# poe.net
KiCad netlist of a schematic drawn in EAGLE
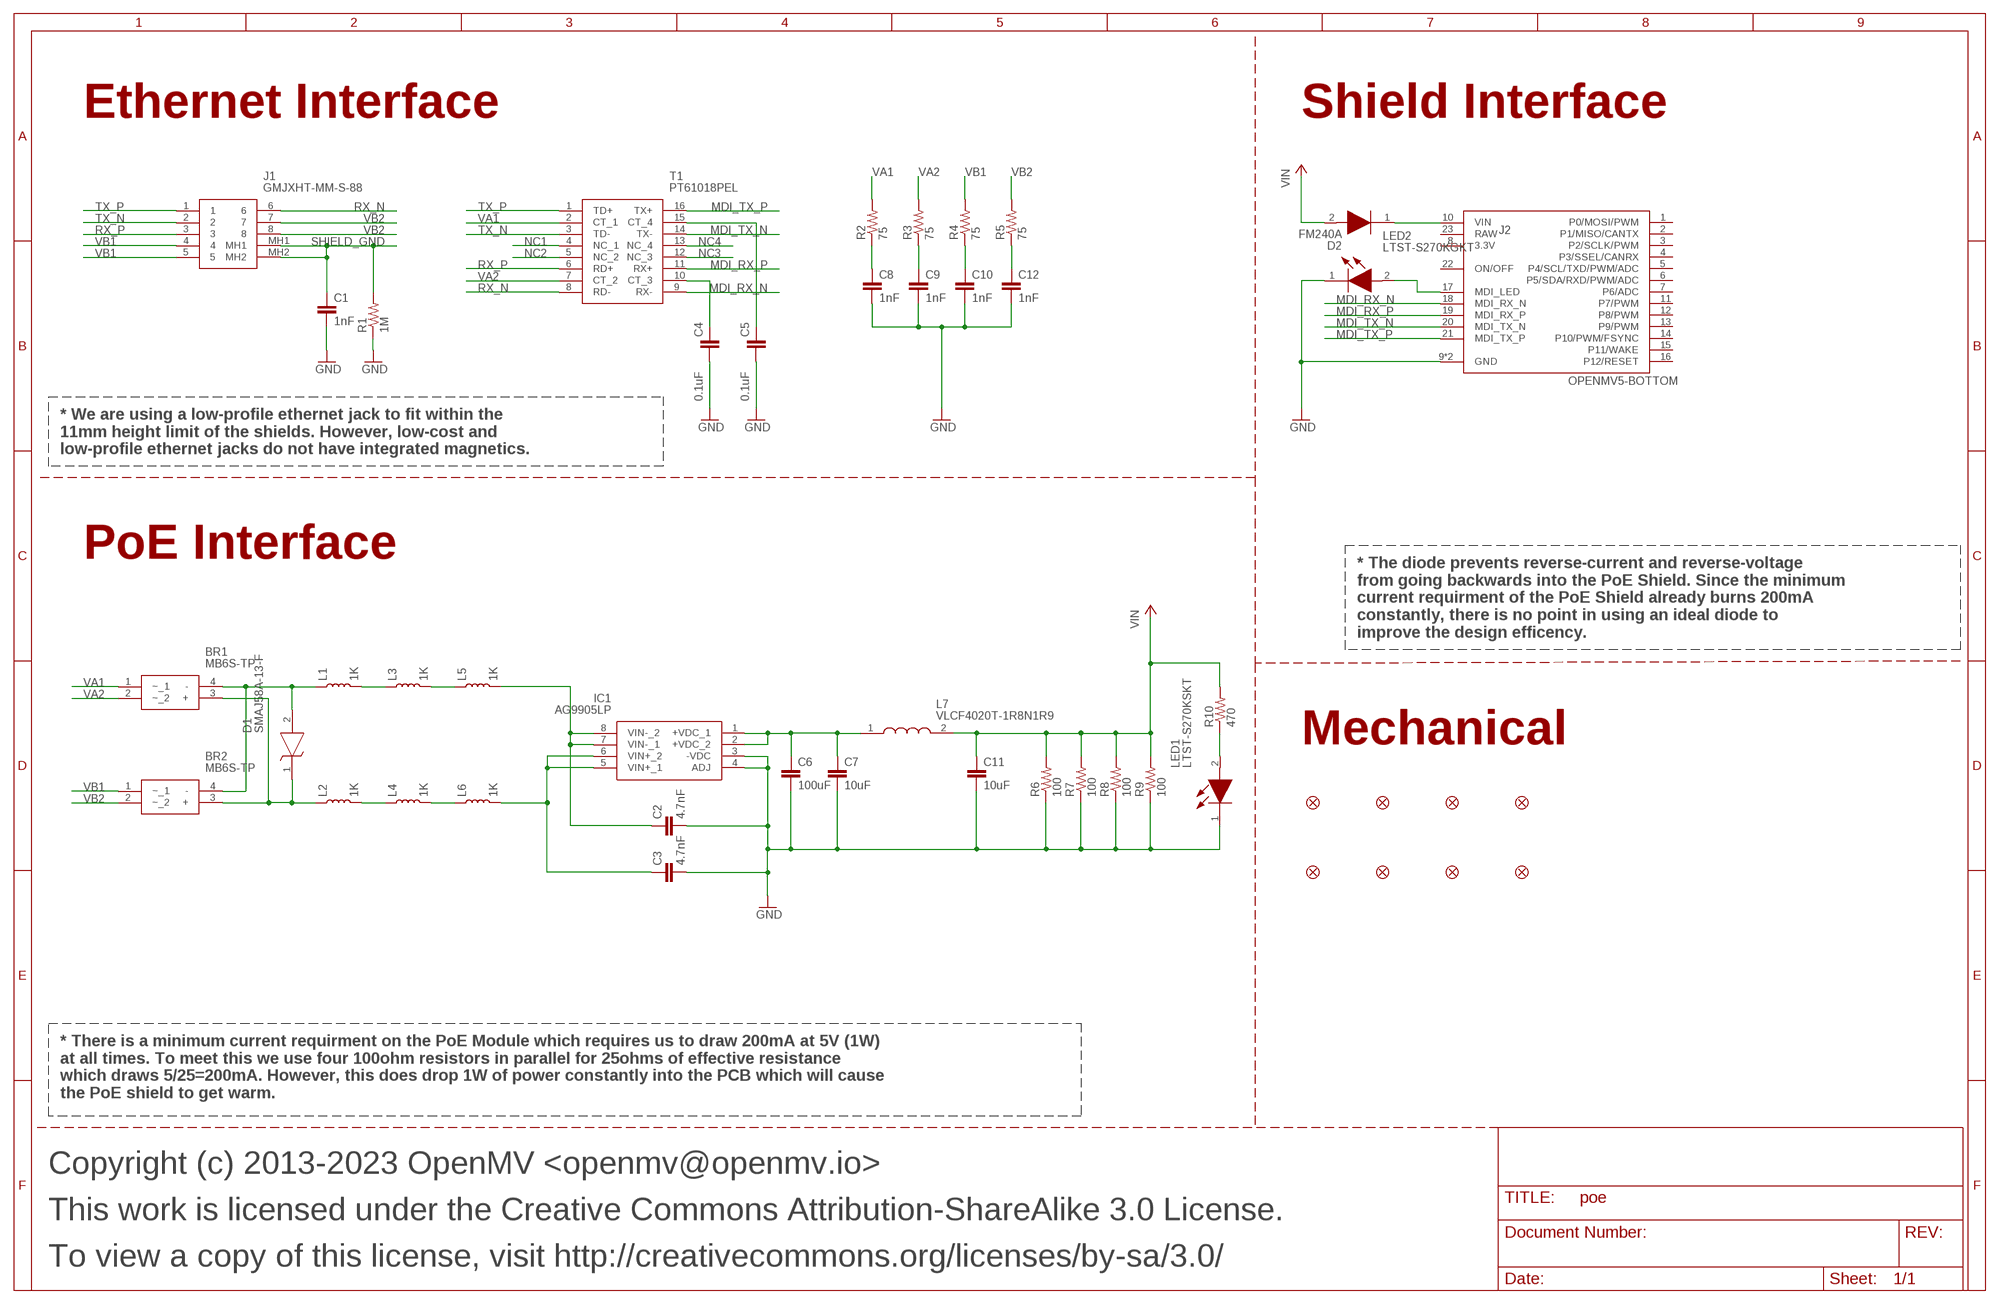
[diagram p0: schematic, sheet 1]

(export (version "E")
  (design (tool "Eeschema 10.0.6"))
  (components
    (comp (ref "BR1")
      (value "MB6S-TP")
      (footprint "eagle-import:SOP254P665X270-4N")
      (fields (field (name "MOUSER_PART_NUMBER") "833-MB6S-TP"))
      (libsource (lib "eagle-import") (part "MB6S-TP"))
    )
    (comp (ref "BR2")
      (value "MB6S-TP")
      (footprint "eagle-import:SOP254P665X270-4N")
      (fields (field (name "MOUSER_PART_NUMBER") "833-MB6S-TP"))
      (libsource (lib "eagle-import") (part "MB6S-TP"))
    )
    (comp (ref "C1")
      (value "1nF")
      (footprint "eagle-import:C1206")
      (fields (field (name "MPN") "1206B102K252CT"))
      (libsource (lib "eagle-import") (part "C-EUC1206"))
    )
    (comp (ref "C2")
      (value "4.7nF")
      (footprint "eagle-import:C1812")
      (fields (field (name "MPN") "202S43W472KV4E"))
      (libsource (lib "eagle-import") (part "C-EUC1812"))
    )
    (comp (ref "C3")
      (value "4.7nF")
      (footprint "eagle-import:C1812")
      (fields (field (name "MPN") "202S43W472KV4E"))
      (libsource (lib "eagle-import") (part "C-EUC1812"))
    )
    (comp (ref "C4")
      (value "0.1uF")
      (footprint "eagle-import:0402")
      (fields (field (name "MPN") "GRM155R71H104KE14D"))
      (libsource (lib "eagle-import") (part "0.1UF-0402-16V-10%"))
    )
    (comp (ref "C5")
      (value "0.1uF")
      (footprint "eagle-import:0402")
      (fields (field (name "MPN") "GRM155R71H104KE14D"))
      (libsource (lib "eagle-import") (part "0.1UF-0402-16V-10%"))
    )
    (comp (ref "C6")
      (value "100uF")
      (footprint "eagle-import:C1206")
      (fields (field (name "MPN") "CL31A107MQHNNWE"))
      (libsource (lib "eagle-import") (part "C-EUC1206"))
    )
    (comp (ref "C7")
      (value "10uF")
      (footprint "eagle-import:C0402")
      (fields (field (name "MPN") "GRM155R60J106ME05D"))
      (libsource (lib "eagle-import") (part "C-EUC0402"))
    )
    (comp (ref "C8")
      (value "1nF")
      (footprint "eagle-import:C1206")
      (fields (field (name "MPN") "1206B102K252CT"))
      (libsource (lib "eagle-import") (part "C-EUC1206"))
    )
    (comp (ref "C9")
      (value "1nF")
      (footprint "eagle-import:C1206")
      (fields (field (name "MPN") "1206B102K252CT"))
      (libsource (lib "eagle-import") (part "C-EUC1206"))
    )
    (comp (ref "C10")
      (value "1nF")
      (footprint "eagle-import:C1206")
      (fields (field (name "MPN") "1206B102K252CT"))
      (libsource (lib "eagle-import") (part "C-EUC1206"))
    )
    (comp (ref "C11")
      (value "10uF")
      (footprint "eagle-import:C0402")
      (fields (field (name "MPN") "GRM155R60J106ME05D"))
      (libsource (lib "eagle-import") (part "C-EUC0402"))
    )
    (comp (ref "C12")
      (value "1nF")
      (footprint "eagle-import:C1206")
      (fields (field (name "MPN") "1206B102K252CT"))
      (libsource (lib "eagle-import") (part "C-EUC1206"))
    )
    (comp (ref "D1")
      (value "SMAJ58A-13-F")
      (footprint "eagle-import:DIOM5226X230N")
      (fields (field (name "MOUSER_PART_NUMBER") "621-SMAJ58A-13-F") (field (name "MPN") "SMAJ58A/TR13"))
      (libsource (lib "eagle-import") (part "SMAJ58A-13-F"))
    )
    (comp (ref "D2")
      (value "FM240A")
      (footprint "eagle-import:DIOM5025X231N")
      (fields (field (name "MOUSER_PART_NUMBER") "583-FM240A"))
      (libsource (lib "eagle-import") (part "FM240A"))
    )
    (comp (ref "FD1")
      (value "FIDUCIAL1X2")
      (footprint "eagle-import:FIDUCIAL-1X2")
      (libsource (lib "eagle-import") (part "FIDUCIAL1X2"))
    )
    (comp (ref "FD2")
      (value "FIDUCIAL1X2")
      (footprint "eagle-import:FIDUCIAL-1X2")
      (libsource (lib "eagle-import") (part "FIDUCIAL1X2"))
    )
    (comp (ref "FD3")
      (value "FIDUCIAL1X2")
      (footprint "eagle-import:FIDUCIAL-1X2")
      (libsource (lib "eagle-import") (part "FIDUCIAL1X2"))
    )
    (comp (ref "FD4")
      (value "FIDUCIAL1X2")
      (footprint "eagle-import:FIDUCIAL-1X2")
      (libsource (lib "eagle-import") (part "FIDUCIAL1X2"))
    )
    (comp (ref "FD5")
      (value "FIDUCIAL1X2")
      (footprint "eagle-import:FIDUCIAL-1X2")
      (libsource (lib "eagle-import") (part "FIDUCIAL1X2"))
    )
    (comp (ref "FD6")
      (value "FIDUCIAL1X2")
      (footprint "eagle-import:FIDUCIAL-1X2")
      (libsource (lib "eagle-import") (part "FIDUCIAL1X2"))
    )
    (comp (ref "FD7")
      (value "FIDUCIAL1X2")
      (footprint "eagle-import:FIDUCIAL-1X2")
      (libsource (lib "eagle-import") (part "FIDUCIAL1X2"))
    )
    (comp (ref "FD8")
      (value "FIDUCIAL1X2")
      (footprint "eagle-import:FIDUCIAL-1X2")
      (libsource (lib "eagle-import") (part "FIDUCIAL1X2"))
    )
    (comp (ref "IC1")
      (value "AG9905LP")
      (footprint "eagle-import:AG9905LP")
      (fields
        (field (name "MANUFACTURER_PART_NUMBER") "Ag9905LP")
        (field (name "MOUSER_PART_NUMBER") "480-AG9905LP")
      )
      (libsource (lib "eagle-import") (part "AG9905LP"))
    )
    (comp (ref "J1")
      (value "GMJXHT-MM-S-88")
      (footprint "eagle-import:GMJXHTMMS88")
      (fields (field (name "MOUSER_PART_NUMBER") "806-GMJXHT-MM-S-88"))
      (libsource (lib "eagle-import") (part "GMJXHT-MM-S-88"))
    )
    (comp (ref "J2")
      (value "OPENMV5-BOTTOM")
      (footprint "eagle-import:OPENMV5-BOTTOM")
      (libsource (lib "eagle-import") (part "OPENMV5-BOTTOM"))
    )
    (comp (ref "L1")
      (value "1K")
      (footprint "eagle-import:0805")
      (fields (field (name "MPN") "2508051027Y1"))
      (libsource (lib "eagle-import") (part "INDUCTOR-0805-3.3UH"))
    )
    (comp (ref "L2")
      (value "1K")
      (footprint "eagle-import:0805")
      (fields (field (name "MPN") "2508051027Y1"))
      (libsource (lib "eagle-import") (part "INDUCTOR-0805-3.3UH"))
    )
    (comp (ref "L3")
      (value "1K")
      (footprint "eagle-import:0805")
      (fields (field (name "MPN") "2508051027Y1"))
      (libsource (lib "eagle-import") (part "INDUCTOR-0805-3.3UH"))
    )
    (comp (ref "L4")
      (value "1K")
      (footprint "eagle-import:0805")
      (fields (field (name "MPN") "2508051027Y1"))
      (libsource (lib "eagle-import") (part "INDUCTOR-0805-3.3UH"))
    )
    (comp (ref "L5")
      (value "1K")
      (footprint "eagle-import:0805")
      (fields (field (name "MPN") "2508051027Y1"))
      (libsource (lib "eagle-import") (part "INDUCTOR-0805-3.3UH"))
    )
    (comp (ref "L6")
      (value "1K")
      (footprint "eagle-import:0805")
      (fields (field (name "MPN") "2508051027Y1"))
      (libsource (lib "eagle-import") (part "INDUCTOR-0805-3.3UH"))
    )
    (comp (ref "L7")
      (value "VLCF4020T-1R8N1R9")
      (footprint "eagle-import:VLCF4020")
      (fields (field (name "MOUSER_PART_NUMBER") "810-VLCF4020T1R8N1R9"))
      (libsource (lib "eagle-import") (part "VLCF4020T-1R8N1R9"))
    )
    (comp (ref "LED1")
      (value "LTST-S270KSKT")
      (footprint "eagle-import:LTSTS270K")
      (fields (field (name "MOUSER_PART_NUMBER") "859-LTST-S270KSKT"))
      (libsource (lib "eagle-import") (part "LTST-S270KSKT"))
    )
    (comp (ref "LED2")
      (value "LTST-S270KGKT")
      (footprint "eagle-import:LTSTS270K")
      (fields (field (name "MOUSER_PART_NUMBER") "859-LTST-S270KGKT"))
      (libsource (lib "eagle-import") (part "LTST-S270KGKT"))
    )
    (comp (ref "R1")
      (value "1M")
      (footprint "eagle-import:R1206")
      (fields (field (name "MPN") "RMCF1206FT1M00"))
      (libsource (lib "eagle-import") (part "R-US_R1206"))
    )
    (comp (ref "R2")
      (value "75")
      (footprint "eagle-import:R0402")
      (fields (field (name "MPN") "CR0402-FX-75R0GLF"))
      (libsource (lib "eagle-import") (part "R-US_R0402"))
    )
    (comp (ref "R3")
      (value "75")
      (footprint "eagle-import:R0402")
      (fields (field (name "MPN") "CR0402-FX-75R0GLF"))
      (libsource (lib "eagle-import") (part "R-US_R0402"))
    )
    (comp (ref "R4")
      (value "75")
      (footprint "eagle-import:R0402")
      (fields (field (name "MPN") "CR0402-FX-75R0GLF"))
      (libsource (lib "eagle-import") (part "R-US_R0402"))
    )
    (comp (ref "R5")
      (value "75")
      (footprint "eagle-import:R0402")
      (fields (field (name "MPN") "CR0402-FX-75R0GLF"))
      (libsource (lib "eagle-import") (part "R-US_R0402"))
    )
    (comp (ref "R6")
      (value "100")
      (footprint "eagle-import:R2512")
      (fields (field (name "MPN") "RC2512JK-07100RL"))
      (libsource (lib "eagle-import") (part "R-US_R2512"))
    )
    (comp (ref "R7")
      (value "100")
      (footprint "eagle-import:R2512")
      (fields (field (name "MPN") "RC2512JK-07100RL"))
      (libsource (lib "eagle-import") (part "R-US_R2512"))
    )
    (comp (ref "R8")
      (value "100")
      (footprint "eagle-import:R2512")
      (fields (field (name "MPN") "RC2512JK-07100RL"))
      (libsource (lib "eagle-import") (part "R-US_R2512"))
    )
    (comp (ref "R9")
      (value "100")
      (footprint "eagle-import:R2512")
      (fields (field (name "MPN") "RC2512JK-07100RL"))
      (libsource (lib "eagle-import") (part "R-US_R2512"))
    )
    (comp (ref "R10")
      (value "470")
      (footprint "eagle-import:R0603")
      (fields (field (name "MPN") "CR0603-FX-4700ELF"))
      (libsource (lib "eagle-import") (part "R-US_R0603"))
    )
    (comp (ref "T1")
      (value "PT61018PEL")
      (footprint "eagle-import:SOIC127P930X565-16N")
      (fields (field (name "MOUSER_PART_NUMBER") "652-PT61018PEL"))
      (libsource (lib "eagle-import") (part "PT61018PEL"))
    )
  )
  (nets
    (net (code "1") (name "/3.3V") (class "Default")
      (node (ref "J2") (pin "8") (pinfunction "3.3V_8") (pintype "power_in"))
    )
    (net (code "2") (name "/MDI_RX_N") (class "Default")
      (node (ref "J2") (pin "18") (pinfunction "MDI_RX_N_18") (pintype "bidirectional"))
      (node (ref "T1") (pin "9") (pinfunction "RX-_9") (pintype "bidirectional"))
    )
    (net (code "3") (name "/MDI_RX_P") (class "Default")
      (node (ref "J2") (pin "19") (pinfunction "MDI_RX_P_19") (pintype "bidirectional"))
      (node (ref "T1") (pin "11") (pinfunction "RX+_11") (pintype "bidirectional"))
    )
    (net (code "4") (name "/MDI_TX_N") (class "Default")
      (node (ref "J2") (pin "20") (pinfunction "MDI_TX_N_20") (pintype "bidirectional"))
      (node (ref "T1") (pin "14") (pinfunction "TX-_14") (pintype "bidirectional"))
    )
    (net (code "5") (name "/MDI_TX_P") (class "Default")
      (node (ref "J2") (pin "21") (pinfunction "MDI_TX_P_21") (pintype "bidirectional"))
      (node (ref "T1") (pin "16") (pinfunction "TX+_16") (pintype "bidirectional"))
    )
    (net (code "6") (name "/NC1") (class "Default")
      (node (ref "T1") (pin "4") (pinfunction "NC_1_4") (pintype "bidirectional"))
    )
    (net (code "7") (name "/NC2") (class "Default")
      (node (ref "T1") (pin "5") (pinfunction "NC_2_5") (pintype "bidirectional"))
    )
    (net (code "8") (name "/NC3") (class "Default")
      (node (ref "T1") (pin "12") (pinfunction "NC_3_12") (pintype "bidirectional"))
    )
    (net (code "9") (name "/NC4") (class "Default")
      (node (ref "T1") (pin "13") (pinfunction "NC_4_13") (pintype "bidirectional"))
    )
    (net (code "10") (name "/RAW") (class "Default")
      (node (ref "J2") (pin "23") (pinfunction "RAW_23") (pintype "power_in"))
    )
    (net (code "11") (name "/RX_N") (class "Default")
      (node (ref "J1") (pin "6") (pinfunction "6_6") (pintype "bidirectional"))
      (node (ref "T1") (pin "8") (pinfunction "RD-_8") (pintype "bidirectional"))
    )
    (net (code "12") (name "/RX_P") (class "Default")
      (node (ref "J1") (pin "3") (pinfunction "3_3") (pintype "bidirectional"))
      (node (ref "T1") (pin "6") (pinfunction "RD+_6") (pintype "bidirectional"))
    )
    (net (code "13") (name "/SHIELD_GND") (class "Default")
      (node (ref "C1") (pin "1") (pinfunction "1_1") (pintype "passive"))
      (node (ref "J1") (pin "MH1") (pinfunction "MH1_MH1") (pintype "bidirectional"))
      (node (ref "J1") (pin "MH2") (pinfunction "MH2_MH2") (pintype "bidirectional"))
      (node (ref "R1") (pin "2") (pinfunction "2_2") (pintype "passive"))
    )
    (net (code "14") (name "/TX_N") (class "Default")
      (node (ref "J1") (pin "2") (pinfunction "2_2") (pintype "bidirectional"))
      (node (ref "T1") (pin "3") (pinfunction "TD-_3") (pintype "bidirectional"))
    )
    (net (code "15") (name "/TX_P") (class "Default")
      (node (ref "J1") (pin "1") (pinfunction "1_1") (pintype "bidirectional"))
      (node (ref "T1") (pin "1") (pinfunction "TD+_1") (pintype "bidirectional"))
    )
    (net (code "16") (name "/VA1") (class "Default")
      (node (ref "BR1") (pin "1") (pinfunction "~{_1}_1") (pintype "bidirectional"))
      (node (ref "R2") (pin "2") (pinfunction "2_2") (pintype "passive"))
      (node (ref "T1") (pin "2") (pinfunction "CT_1_2") (pintype "bidirectional"))
    )
    (net (code "17") (name "/VA2") (class "Default")
      (node (ref "BR1") (pin "2") (pinfunction "~{_2}_2") (pintype "bidirectional"))
      (node (ref "R3") (pin "2") (pinfunction "2_2") (pintype "passive"))
      (node (ref "T1") (pin "7") (pinfunction "CT_2_7") (pintype "bidirectional"))
    )
    (net (code "18") (name "/VB1") (class "Default")
      (node (ref "BR2") (pin "1") (pinfunction "~{_1}_1") (pintype "bidirectional"))
      (node (ref "J1") (pin "4") (pinfunction "4_4") (pintype "bidirectional"))
      (node (ref "J1") (pin "5") (pinfunction "5_5") (pintype "bidirectional"))
      (node (ref "R4") (pin "2") (pinfunction "2_2") (pintype "passive"))
    )
    (net (code "19") (name "/VB2") (class "Default")
      (node (ref "BR2") (pin "2") (pinfunction "~{_2}_2") (pintype "bidirectional"))
      (node (ref "J1") (pin "7") (pinfunction "7_7") (pintype "bidirectional"))
      (node (ref "J1") (pin "8") (pinfunction "8_8") (pintype "bidirectional"))
      (node (ref "R5") (pin "2") (pinfunction "2_2") (pintype "passive"))
    )
    (net (code "20") (name "GND") (class "Default")
      (node (ref "C1") (pin "2") (pinfunction "2_2") (pintype "passive"))
      (node (ref "C10") (pin "2") (pinfunction "2_2") (pintype "passive"))
      (node (ref "C11") (pin "2") (pinfunction "2_2") (pintype "passive"))
      (node (ref "C12") (pin "2") (pinfunction "2_2") (pintype "passive"))
      (node (ref "C2") (pin "2") (pinfunction "2_2") (pintype "passive"))
      (node (ref "C3") (pin "2") (pinfunction "2_2") (pintype "passive"))
      (node (ref "C4") (pin "2") (pinfunction "2_2") (pintype "passive"))
      (node (ref "C5") (pin "2") (pinfunction "2_2") (pintype "passive"))
      (node (ref "C6") (pin "2") (pinfunction "2_2") (pintype "passive"))
      (node (ref "C7") (pin "2") (pinfunction "2_2") (pintype "passive"))
      (node (ref "C8") (pin "2") (pinfunction "2_2") (pintype "passive"))
      (node (ref "C9") (pin "2") (pinfunction "2_2") (pintype "passive"))
      (node (ref "IC1") (pin "3") (pinfunction "-VDC_3") (pintype "bidirectional"))
      (node (ref "IC1") (pin "4") (pinfunction "ADJ_4") (pintype "bidirectional"))
      (node (ref "J2") (pin "24") (pinfunction "GND_24") (pintype "power_in"))
      (node (ref "J2") (pin "9") (pinfunction "GND_9") (pintype "power_in"))
      (node (ref "LED1") (pin "1") (pinfunction "K_1") (pintype "bidirectional"))
      (node (ref "LED2") (pin "1") (pinfunction "K_1") (pintype "bidirectional"))
      (node (ref "R1") (pin "1") (pinfunction "1_1") (pintype "passive"))
      (node (ref "R6") (pin "1") (pinfunction "1_1") (pintype "passive"))
      (node (ref "R7") (pin "1") (pinfunction "1_1") (pintype "passive"))
      (node (ref "R8") (pin "1") (pinfunction "1_1") (pintype "passive"))
      (node (ref "R9") (pin "1") (pinfunction "1_1") (pintype "passive"))
    )
    (net (code "21") (name "Net-(BR1-+)") (class "Default")
      (node (ref "BR1") (pin "3") (pinfunction "+_3") (pintype "bidirectional"))
      (node (ref "BR2") (pin "3") (pinfunction "+_3") (pintype "bidirectional"))
      (node (ref "D1") (pin "1") (pinfunction "K_1") (pintype "bidirectional"))
      (node (ref "L2") (pin "1") (pinfunction "1_1") (pintype "passive"))
    )
    (net (code "22") (name "Net-(BR1--)") (class "Default")
      (node (ref "BR1") (pin "4") (pinfunction "-_4") (pintype "bidirectional"))
      (node (ref "BR2") (pin "4") (pinfunction "-_4") (pintype "bidirectional"))
      (node (ref "D1") (pin "2") (pinfunction "A_2") (pintype "bidirectional"))
      (node (ref "L1") (pin "1") (pinfunction "1_1") (pintype "passive"))
    )
    (net (code "23") (name "Net-(C8-Pad1)") (class "Default")
      (node (ref "C8") (pin "1") (pinfunction "1_1") (pintype "passive"))
      (node (ref "R2") (pin "1") (pinfunction "1_1") (pintype "passive"))
    )
    (net (code "24") (name "Net-(C9-Pad1)") (class "Default")
      (node (ref "C9") (pin "1") (pinfunction "1_1") (pintype "passive"))
      (node (ref "R3") (pin "1") (pinfunction "1_1") (pintype "passive"))
    )
    (net (code "25") (name "Net-(C10-Pad1)") (class "Default")
      (node (ref "C10") (pin "1") (pinfunction "1_1") (pintype "passive"))
      (node (ref "R4") (pin "1") (pinfunction "1_1") (pintype "passive"))
    )
    (net (code "26") (name "Net-(C12-Pad1)") (class "Default")
      (node (ref "C12") (pin "1") (pinfunction "1_1") (pintype "passive"))
      (node (ref "R5") (pin "1") (pinfunction "1_1") (pintype "passive"))
    )
    (net (code "27") (name "Net-(D2-K)") (class "Default")
      (node (ref "D2") (pin "1") (pinfunction "K_1") (pintype "bidirectional"))
      (node (ref "J2") (pin "10") (pinfunction "VIN_10") (pintype "power_in"))
    )
    (net (code "28") (name "Net-(IC1-+VDC_1)") (class "Default")
      (node (ref "C6") (pin "1") (pinfunction "1_1") (pintype "passive"))
      (node (ref "C7") (pin "1") (pinfunction "1_1") (pintype "passive"))
      (node (ref "IC1") (pin "1") (pinfunction "+VDC_1_1") (pintype "bidirectional"))
      (node (ref "IC1") (pin "2") (pinfunction "+VDC_2_2") (pintype "bidirectional"))
      (node (ref "L7") (pin "1") (pinfunction "1_1") (pintype "bidirectional"))
    )
    (net (code "29") (name "Net-(IC1-VIN+_1)") (class "Default")
      (node (ref "C3") (pin "1") (pinfunction "1_1") (pintype "passive"))
      (node (ref "IC1") (pin "5") (pinfunction "VIN+_1_5") (pintype "bidirectional"))
      (node (ref "IC1") (pin "6") (pinfunction "VIN+_2_6") (pintype "bidirectional"))
      (node (ref "L6") (pin "2") (pinfunction "2_2") (pintype "passive"))
    )
    (net (code "30") (name "Net-(IC1-VIN-_1)") (class "Default")
      (node (ref "C2") (pin "1") (pinfunction "1_1") (pintype "passive"))
      (node (ref "IC1") (pin "7") (pinfunction "VIN-_1_7") (pintype "bidirectional"))
      (node (ref "IC1") (pin "8") (pinfunction "VIN-_2_8") (pintype "bidirectional"))
      (node (ref "L5") (pin "2") (pinfunction "2_2") (pintype "passive"))
    )
    (net (code "31") (name "Net-(J2-MDI_LED)") (class "Default")
      (node (ref "J2") (pin "17") (pinfunction "MDI_LED_17") (pintype "bidirectional"))
      (node (ref "LED2") (pin "2") (pinfunction "A_2") (pintype "bidirectional"))
    )
    (net (code "32") (name "Net-(L1-Pad2)") (class "Default")
      (node (ref "L1") (pin "2") (pinfunction "2_2") (pintype "passive"))
      (node (ref "L3") (pin "1") (pinfunction "1_1") (pintype "passive"))
    )
    (net (code "33") (name "Net-(L2-Pad2)") (class "Default")
      (node (ref "L2") (pin "2") (pinfunction "2_2") (pintype "passive"))
      (node (ref "L4") (pin "1") (pinfunction "1_1") (pintype "passive"))
    )
    (net (code "34") (name "Net-(L3-Pad2)") (class "Default")
      (node (ref "L3") (pin "2") (pinfunction "2_2") (pintype "passive"))
      (node (ref "L5") (pin "1") (pinfunction "1_1") (pintype "passive"))
    )
    (net (code "35") (name "Net-(L4-Pad2)") (class "Default")
      (node (ref "L4") (pin "2") (pinfunction "2_2") (pintype "passive"))
      (node (ref "L6") (pin "1") (pinfunction "1_1") (pintype "passive"))
    )
    (net (code "36") (name "Net-(LED1-A)") (class "Default")
      (node (ref "LED1") (pin "2") (pinfunction "A_2") (pintype "bidirectional"))
      (node (ref "R10") (pin "1") (pinfunction "1_1") (pintype "passive"))
    )
    (net (code "37") (name "Net-(T1-CT_3)") (class "Default")
      (node (ref "C4") (pin "1") (pinfunction "1_1") (pintype "passive"))
      (node (ref "T1") (pin "10") (pinfunction "CT_3_10") (pintype "bidirectional"))
    )
    (net (code "38") (name "Net-(T1-CT_4)") (class "Default")
      (node (ref "C5") (pin "1") (pinfunction "1_1") (pintype "passive"))
      (node (ref "T1") (pin "15") (pinfunction "CT_4_15") (pintype "bidirectional"))
    )
    (net (code "39") (name "VIN") (class "Default")
      (node (ref "C11") (pin "1") (pinfunction "1_1") (pintype "passive"))
      (node (ref "D2") (pin "2") (pinfunction "A_2") (pintype "bidirectional"))
      (node (ref "L7") (pin "2") (pinfunction "2_2") (pintype "bidirectional"))
      (node (ref "R10") (pin "2") (pinfunction "2_2") (pintype "passive"))
      (node (ref "R6") (pin "2") (pinfunction "2_2") (pintype "passive"))
      (node (ref "R7") (pin "2") (pinfunction "2_2") (pintype "passive"))
      (node (ref "R8") (pin "2") (pinfunction "2_2") (pintype "passive"))
      (node (ref "R9") (pin "2") (pinfunction "2_2") (pintype "passive"))
    )
    (net (code "40") (name "unconnected-(J2-ON{slash}OFF-Pad22)") (class "Default")
      (node (ref "J2") (pin "22") (pinfunction "ON/OFF_22") (pintype "bidirectional"))
    )
    (net (code "41") (name "unconnected-(J2-P0{slash}MOSI{slash}PWM-Pad1)") (class "Default")
      (node (ref "J2") (pin "1") (pinfunction "P0/MOSI/PWM_1") (pintype "bidirectional"))
    )
    (net (code "42") (name "unconnected-(J2-P1{slash}MISO{slash}CANTX-Pad2)") (class "Default")
      (node (ref "J2") (pin "2") (pinfunction "P1/MISO/CANTX_2") (pintype "bidirectional"))
    )
    (net (code "43") (name "unconnected-(J2-P2{slash}SCLK{slash}PWM-Pad3)") (class "Default")
      (node (ref "J2") (pin "3") (pinfunction "P2/SCLK/PWM_3") (pintype "bidirectional"))
    )
    (net (code "44") (name "unconnected-(J2-P3{slash}SSEL{slash}CANRX-Pad4)") (class "Default")
      (node (ref "J2") (pin "4") (pinfunction "P3/SSEL/CANRX_4") (pintype "bidirectional"))
    )
    (net (code "45") (name "unconnected-(J2-P4{slash}SCL{slash}TXD{slash}PWM{slash}ADC-Pad5)") (class "Default")
      (node (ref "J2") (pin "5") (pinfunction "P4/SCL/TXD/PWM/ADC_5") (pintype "bidirectional"))
    )
    (net (code "46") (name "unconnected-(J2-P5{slash}SDA{slash}RXD{slash}PWM{slash}ADC-Pad6)") (class "Default")
      (node (ref "J2") (pin "6") (pinfunction "P5/SDA/RXD/PWM/ADC_6") (pintype "bidirectional"))
    )
    (net (code "47") (name "unconnected-(J2-P6{slash}ADC-Pad7)") (class "Default")
      (node (ref "J2") (pin "7") (pinfunction "P6/ADC_7") (pintype "bidirectional"))
    )
    (net (code "48") (name "unconnected-(J2-P7{slash}PWM-Pad11)") (class "Default")
      (node (ref "J2") (pin "11") (pinfunction "P7/PWM_11") (pintype "bidirectional"))
    )
    (net (code "49") (name "unconnected-(J2-P8{slash}PWM-Pad12)") (class "Default")
      (node (ref "J2") (pin "12") (pinfunction "P8/PWM_12") (pintype "bidirectional"))
    )
    (net (code "50") (name "unconnected-(J2-P9{slash}PWM-Pad13)") (class "Default")
      (node (ref "J2") (pin "13") (pinfunction "P9/PWM_13") (pintype "bidirectional"))
    )
    (net (code "51") (name "unconnected-(J2-P10{slash}PWM{slash}FSYNC-Pad14)") (class "Default")
      (node (ref "J2") (pin "14") (pinfunction "P10/PWM/FSYNC_14") (pintype "bidirectional"))
    )
    (net (code "52") (name "unconnected-(J2-P11{slash}WAKE-Pad15)") (class "Default")
      (node (ref "J2") (pin "15") (pinfunction "P11/WAKE_15") (pintype "bidirectional"))
    )
    (net (code "53") (name "unconnected-(J2-P12{slash}RESET-Pad16)") (class "Default")
      (node (ref "J2") (pin "16") (pinfunction "P12/RESET_16") (pintype "bidirectional"))
    )
  )
)
